# SCH_Embedded_Watch_2023-10-23.net
KiCad netlist of a schematic drawn in EasyEDA
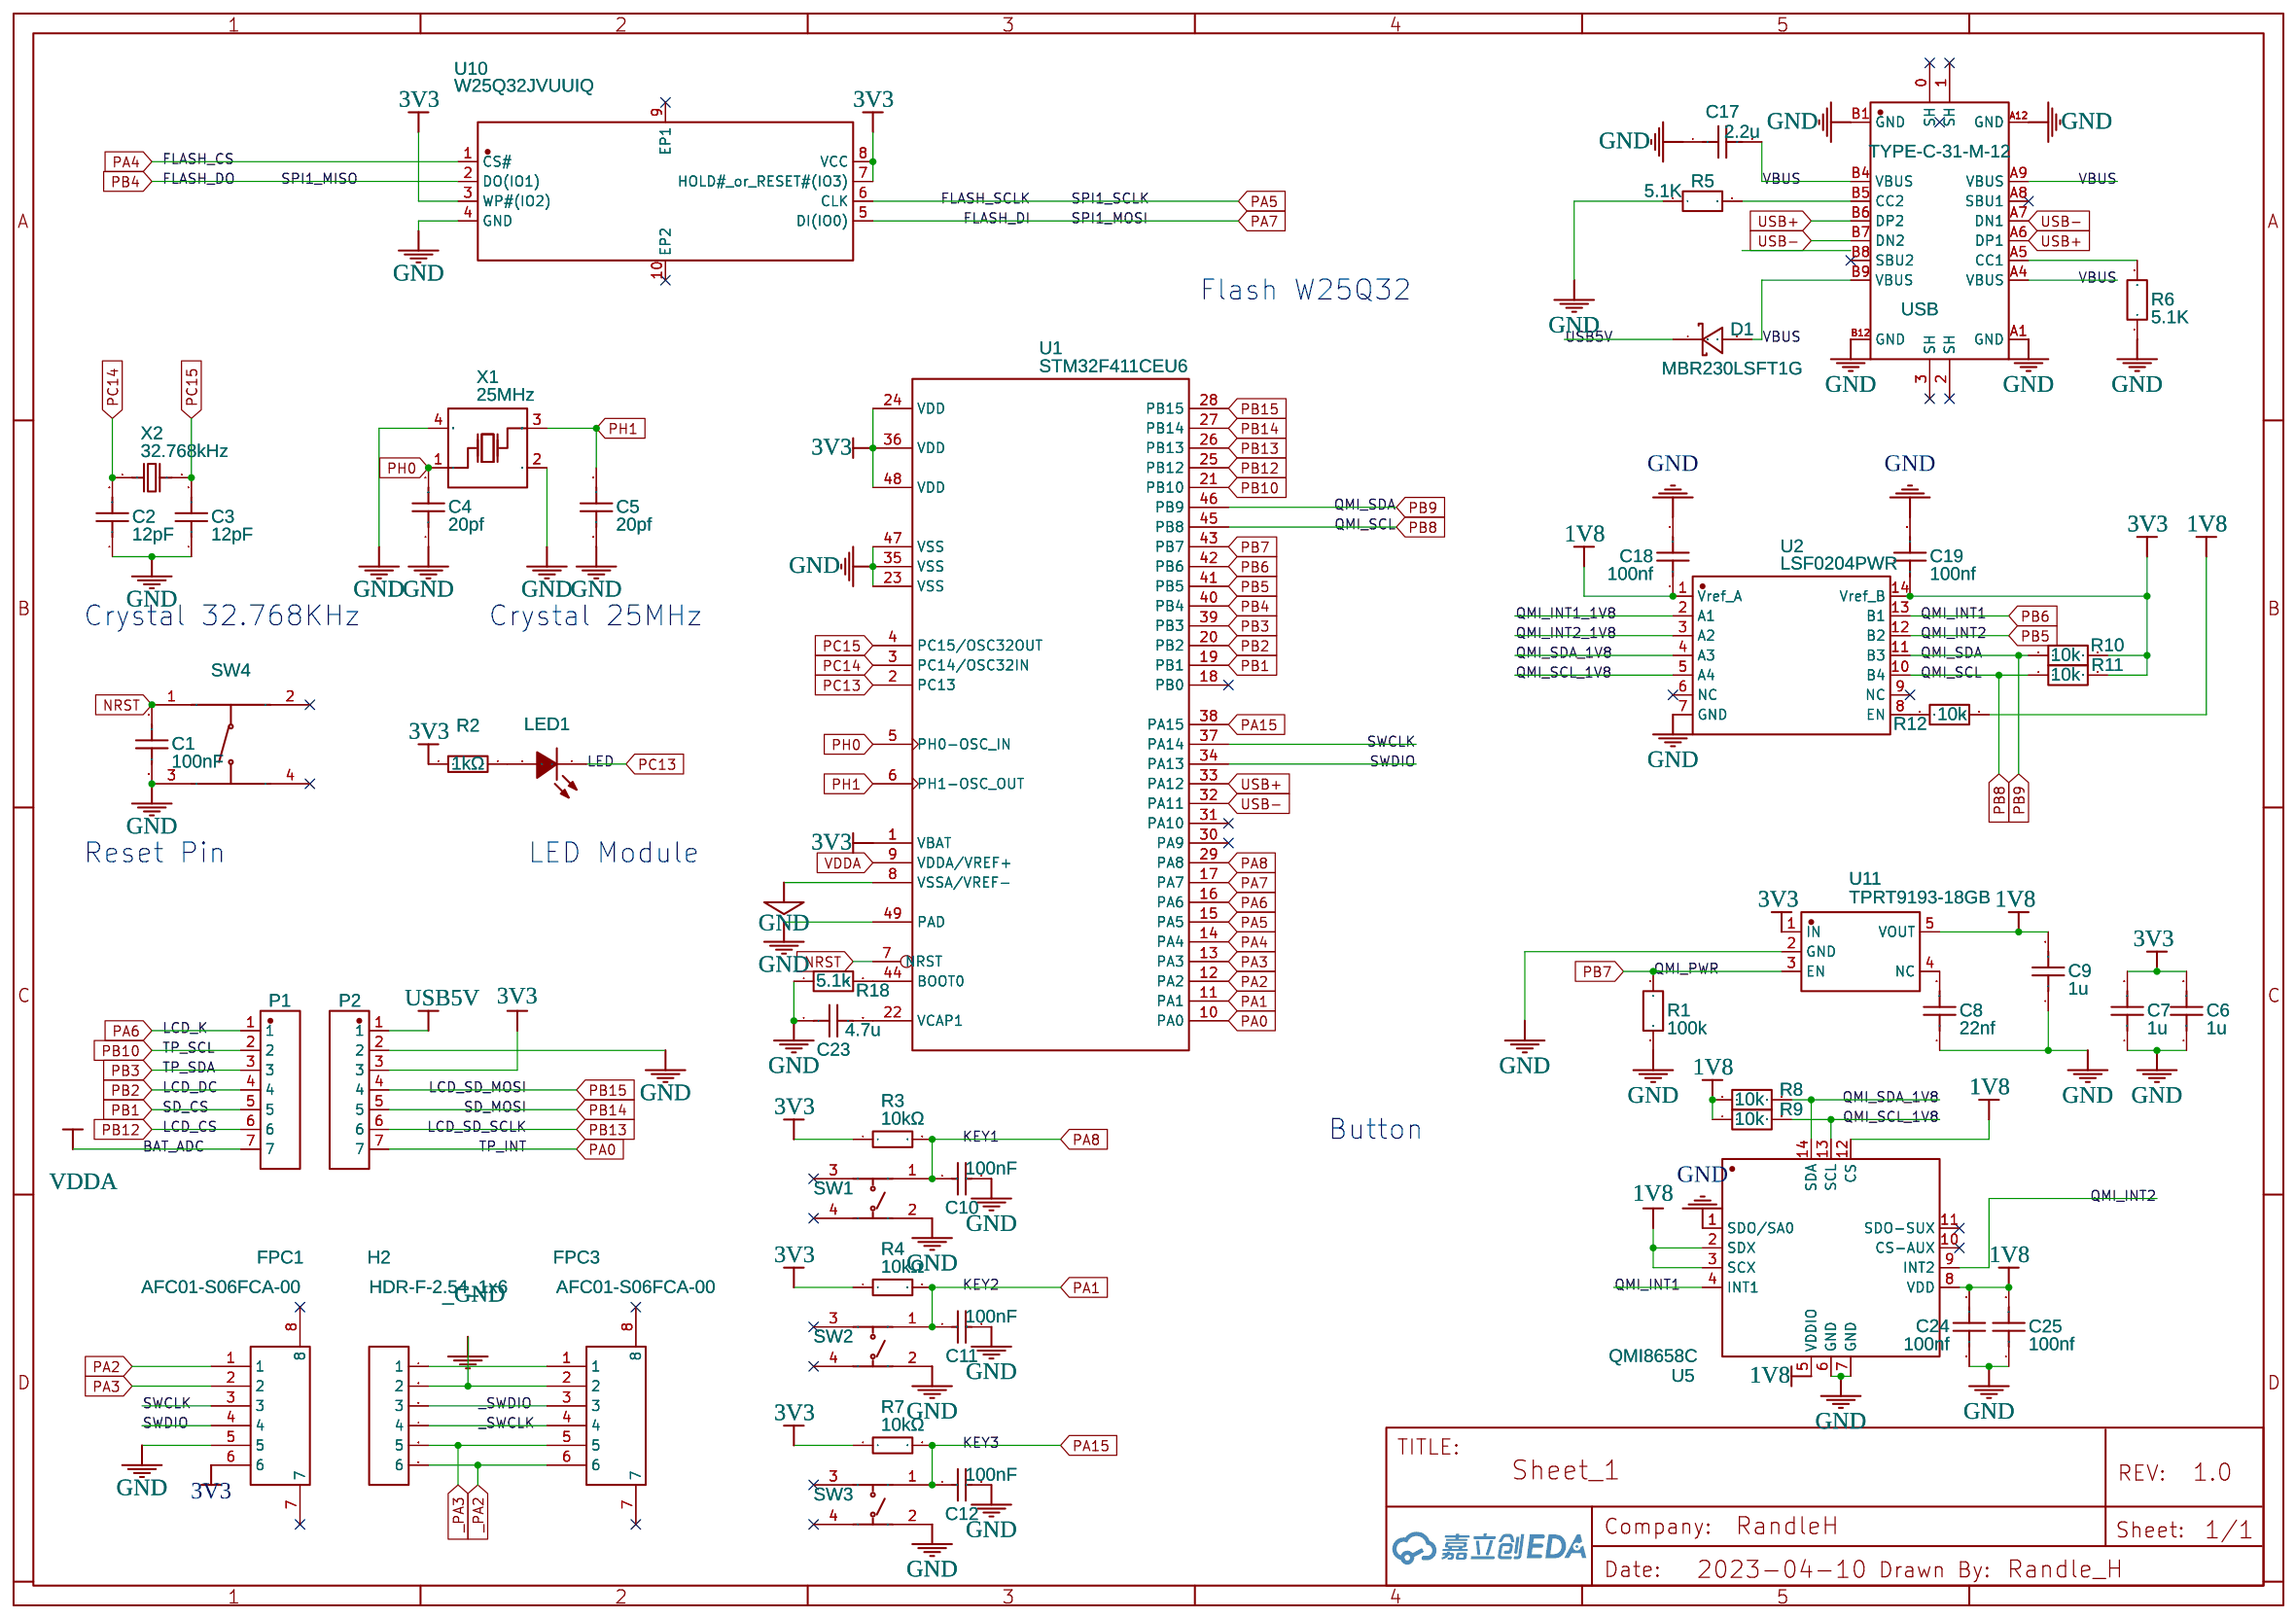
[diagram p0: schematic sheet]

(export (version "E")
  (design (tool "Eeschema 10.0.6"))
  (components
    (comp (ref "C1")
      (value "100nF")
      (fields
        (field (name "Manufacturer Part") "CL05B104KB54PNC")
        (field (name "Manufacturer") "SAMSUNG(三星)")
      )
      (libsource (lib "") (part "CL05B104KB54PNC"))
    )
    (comp (ref "C2")
      (value "12pF")
      (fields
        (field (name "Manufacturer Part") "CC0201JRNPO9BN120")
        (field (name "Manufacturer") "YAGEO(国巨)")
      )
      (libsource (lib "") (part "CC0201JRNPO9BN120"))
    )
    (comp (ref "C3")
      (value "12pF")
      (fields
        (field (name "Manufacturer Part") "CC0201JRNPO9BN120")
        (field (name "Manufacturer") "YAGEO(国巨)")
      )
      (libsource (lib "") (part "CC0201JRNPO9BN120"))
    )
    (comp (ref "C4") (value "20pf") (libsource (lib "") (part "C_0603_US")))
    (comp (ref "C5") (value "20pf") (libsource (lib "") (part "C_0603_US")))
    (comp (ref "C6") (value "1u") (libsource (lib "") (part "C_0603_US")))
    (comp (ref "C7") (value "1u") (libsource (lib "") (part "C_0603_US")))
    (comp (ref "C8") (value "22nf") (libsource (lib "") (part "C_0603_US")))
    (comp (ref "C9") (value "1u") (libsource (lib "") (part "C_0603_US")))
    (comp (ref "C10")
      (value "100nF")
      (fields
        (field (name "Manufacturer Part") "CL05B104KO5NNNC")
        (field (name "Manufacturer") "SAMSUNG(三星)")
      )
      (libsource (lib "") (part "CL05B104KO5NNNC"))
    )
    (comp (ref "C11")
      (value "100nF")
      (fields
        (field (name "Manufacturer Part") "CL05B104KO5NNNC")
        (field (name "Manufacturer") "SAMSUNG(三星)")
      )
      (libsource (lib "") (part "CL05B104KO5NNNC"))
    )
    (comp (ref "C12")
      (value "100nF")
      (fields
        (field (name "Manufacturer Part") "CL05B104KO5NNNC")
        (field (name "Manufacturer") "SAMSUNG(三星)")
      )
      (libsource (lib "") (part "CL05B104KO5NNNC"))
    )
    (comp (ref "C17") (value "2.2u") (libsource (lib "") (part "C_0201_US_2")))
    (comp (ref "C18") (value "100nf") (libsource (lib "") (part "C_0201_US")))
    (comp (ref "C19") (value "100nf") (libsource (lib "") (part "C_0201_US_3")))
    (comp (ref "C23") (value "4.7u") (libsource (lib "") (part "C_0201_US_2")))
    (comp (ref "C24") (value "100nf") (libsource (lib "") (part "C_0201_US_1")))
    (comp (ref "C25") (value "100nf") (libsource (lib "") (part "C_0201_US_3")))
    (comp (ref "D1")
      (value "MBR230LSFT1G")
      (fields (field (name "Manufacturer") "onsemi(安森美)"))
      (libsource (lib "") (part "MBR230LSFT1G"))
    )
    (comp (ref "FPC1")
      (value "AFC01-S06FCA-00")
      (fields (field (name "Manufacturer") "JS(钜硕电子)"))
      (libsource (lib "") (part "AFC01-S06FCA-00"))
    )
    (comp (ref "FPC3")
      (value "AFC01-S06FCA-00")
      (fields (field (name "Manufacturer") "JS(钜硕电子)"))
      (libsource (lib "") (part "AFC01-S06FCA-00"))
    )
    (comp (ref "H2") (value "HDR-F-2.54_1x6") (libsource (lib "") (part "HDR-F-2.54_1x6")))
    (comp (ref "LED1")
      (value "FC-F1005HOK-600H5")
      (fields (field (name "Manufacturer Part") "NCD0402O1") (field (name "Manufacturer") "国星光电"))
      (libsource (lib "") (part "FC-F1005HOK-600H5"))
    )
    (comp (ref "P1")
      (value "PM2.54-1*7")
      (fields
        (field (name "Manufacturer Part") "X6511WVS-07H-C60D48R1")
        (field (name "Manufacturer") "XKB Connectivity(中国星坤)")
      )
      (libsource (lib "") (part "PM2.54-1*7_1"))
    )
    (comp (ref "P2")
      (value "PM2.54-1*7")
      (fields
        (field (name "Manufacturer Part") "X6511WVS-07H-C60D48R1")
        (field (name "Manufacturer") "XKB Connectivity(中国星坤)")
      )
      (libsource (lib "") (part "PM2.54-1*7"))
    )
    (comp (ref "R1") (value "100k") (libsource (lib "") (part "R_0201_EU_2")))
    (comp (ref "R2")
      (value "1kΩ")
      (fields
        (field (name "Manufacturer Part") "0402WGF1001TCE")
        (field (name "Manufacturer") "UNI-ROYAL(厚声)")
      )
      (libsource (lib "") (part "0402WGF1001TCE"))
    )
    (comp (ref "R3")
      (value "10kΩ")
      (fields
        (field (name "Manufacturer Part") "0402WGF1002TCE")
        (field (name "Manufacturer") "UNI-ROYAL(厚声)")
      )
      (libsource (lib "") (part "0402WGF1002TCE"))
    )
    (comp (ref "R4")
      (value "10kΩ")
      (fields
        (field (name "Manufacturer Part") "0402WGF1002TCE")
        (field (name "Manufacturer") "UNI-ROYAL(厚声)")
      )
      (libsource (lib "") (part "0402WGF1002TCE"))
    )
    (comp (ref "R5") (value "5.1K") (libsource (lib "") (part "R_0603_EU")))
    (comp (ref "R6") (value "5.1K") (libsource (lib "") (part "R_0603_EU_1")))
    (comp (ref "R7")
      (value "10kΩ")
      (fields
        (field (name "Manufacturer Part") "0402WGF1002TCE")
        (field (name "Manufacturer") "UNI-ROYAL(厚声)")
      )
      (libsource (lib "") (part "0402WGF1002TCE"))
    )
    (comp (ref "R8") (value "10k") (libsource (lib "") (part "R_0201_EU_1")))
    (comp (ref "R9") (value "10k") (libsource (lib "") (part "R_0201_EU_1")))
    (comp (ref "R10") (value "10k") (libsource (lib "") (part "R_0201_EU_1")))
    (comp (ref "R11") (value "10k") (libsource (lib "") (part "R_0201_EU_1")))
    (comp (ref "R12") (value "10k") (libsource (lib "") (part "R_0201_EU")))
    (comp (ref "R18") (value "5.1k") (libsource (lib "") (part "R_0201_EU_1")))
    (comp (ref "SW1")
      (value "EVQPUD02K")
      (fields (field (name "Manufacturer") "PANASONIC(松下)"))
      (libsource (lib "") (part "EVQPUD02K"))
    )
    (comp (ref "SW2")
      (value "EVQPUD02K")
      (fields (field (name "Manufacturer") "PANASONIC(松下)"))
      (libsource (lib "") (part "EVQPUD02K"))
    )
    (comp (ref "SW3")
      (value "EVQPUD02K")
      (fields (field (name "Manufacturer") "PANASONIC(松下)"))
      (libsource (lib "") (part "EVQPUD02K"))
    )
    (comp (ref "SW4")
      (value "PTS830GM140SMTRLFS")
      (fields (field (name "Manufacturer") "C&K"))
      (libsource (lib "") (part "PTS830GM140SMTRLFS"))
    )
    (comp (ref "U1")
      (value "STM32F411CEU6")
      (fields (field (name "Manufacturer") "ST(意法半导体)"))
      (libsource (lib "") (part "STM32F411CEU6"))
    )
    (comp (ref "U2")
      (value "LSF0204PWR")
      (fields (field (name "Manufacturer") "TI(德州仪器)"))
      (libsource (lib "") (part "LSF0204PWR"))
    )
    (comp (ref "U5")
      (value "QMI8658C")
      (fields (field (name "Manufacturer") "QST(上海矽睿)"))
      (libsource (lib "") (part "QMI8658C"))
    )
    (comp (ref "U10")
      (value "W25Q32JVUUIQ")
      (fields (field (name "Manufacturer") "WINBOND(华邦)"))
      (libsource (lib "") (part "W25Q32JVUUIQ"))
    )
    (comp (ref "U11")
      (value "TPRT9193-18GB")
      (fields (field (name "Manufacturer") "TECH PUBLIC(台舟)"))
      (libsource (lib "") (part "TPRT9193-18GB"))
    )
    (comp (ref "USB")
      (value "TYPE-C-31-M-12")
      (fields (field (name "Manufacturer") "韩国韩荣"))
      (libsource (lib "") (part "TYPE-C-31-M-12"))
    )
    (comp (ref "X1")
      (value "25MHz")
      (fields (field (name "Manufacturer Part") "TAXM25M4RLBCCT2T") (field (name "Manufacturer") "TAE(雅晶鑫)"))
      (libsource (lib "") (part "SMD-3225_4P25MHZ20PF10PPM-40&#126;+85℃"))
    )
    (comp (ref "X2")
      (value "32.768kHz")
      (fields (field (name "Manufacturer Part") "Q13FC1350000400") (field (name "Manufacturer") "EPSON(爱普生)"))
      (libsource (lib "") (part "Q13FC1350000400"))
    )
  )
  (nets
    (net (code "1") (name "/QMI_INT1_1V8") (class "Default")
      (node (ref "U2") (pin "2") (pinfunction "A1_2") (pintype "unspecified"))
    )
    (net (code "2") (name "/QMI_INT2_1V8") (class "Default")
      (node (ref "U2") (pin "3") (pinfunction "A2_3") (pintype "unspecified"))
    )
    (net (code "3") (name "/QMI_SCL_1V8") (class "Default")
      (node (ref "R9") (pin "2") (pinfunction "2_2") (pintype "unspecified"))
      (node (ref "U2") (pin "5") (pinfunction "A4_5") (pintype "unspecified"))
      (node (ref "U5") (pin "13") (pinfunction "SCL_13") (pintype "unspecified"))
    )
    (net (code "4") (name "/QMI_SDA_1V8") (class "Default")
      (node (ref "R8") (pin "2") (pinfunction "2_2") (pintype "unspecified"))
      (node (ref "U2") (pin "4") (pinfunction "A3_4") (pintype "unspecified"))
      (node (ref "U5") (pin "14") (pinfunction "SDA_14") (pintype "unspecified"))
    )
    (net (code "5") (name "/SWCLK") (class "Default")
      (node (ref "FPC1") (pin "3") (pinfunction "3_3") (pintype "unspecified"))
      (node (ref "U1") (pin "37") (pinfunction "PA14_37") (pintype "unspecified"))
    )
    (net (code "6") (name "/SWDIO") (class "Default")
      (node (ref "FPC1") (pin "4") (pinfunction "4_4") (pintype "unspecified"))
      (node (ref "U1") (pin "34") (pinfunction "PA13_34") (pintype "unspecified"))
    )
    (net (code "7") (name "/VBUS") (class "Default")
      (node (ref "C17") (pin "2") (pinfunction "2_2") (pintype "unspecified"))
      (node (ref "D1") (pin "2") (pinfunction "A_2") (pintype "unspecified"))
      (node (ref "USB") (pin "A4") (pinfunction "VBUS_A4") (pintype "unspecified"))
      (node (ref "USB") (pin "A9") (pinfunction "VBUS_A9") (pintype "unspecified"))
      (node (ref "USB") (pin "B4") (pinfunction "VBUS_B4") (pintype "unspecified"))
      (node (ref "USB") (pin "B9") (pinfunction "VBUS_B9") (pintype "unspecified"))
    )
    (net (code "8") (name "/_SWCLK") (class "Default")
      (node (ref "FPC3") (pin "4") (pinfunction "4_4") (pintype "unspecified"))
      (node (ref "H2") (pin "4") (pinfunction "4_4") (pintype "input"))
    )
    (net (code "9") (name "/_SWDIO") (class "Default")
      (node (ref "FPC3") (pin "3") (pinfunction "3_3") (pintype "unspecified"))
      (node (ref "H2") (pin "3") (pinfunction "3_3") (pintype "input"))
    )
    (net (code "10") (name "1V8") (class "Default")
      (node (ref "C18") (pin "1") (pinfunction "1_1") (pintype "unspecified"))
      (node (ref "C24") (pin "1") (pinfunction "1_1") (pintype "unspecified"))
      (node (ref "C25") (pin "2") (pinfunction "2_2") (pintype "unspecified"))
      (node (ref "C9") (pin "2") (pinfunction "2_2") (pintype "unspecified"))
      (node (ref "R12") (pin "1") (pinfunction "1_1") (pintype "unspecified"))
      (node (ref "R8") (pin "1") (pinfunction "1_1") (pintype "unspecified"))
      (node (ref "R9") (pin "1") (pinfunction "1_1") (pintype "unspecified"))
      (node (ref "U11") (pin "5") (pinfunction "VOUT_5") (pintype "unspecified"))
      (node (ref "U2") (pin "1") (pinfunction "Vref_A_1") (pintype "unspecified"))
      (node (ref "U5") (pin "12") (pinfunction "CS_12") (pintype "unspecified"))
      (node (ref "U5") (pin "2") (pinfunction "SDX_2") (pintype "unspecified"))
      (node (ref "U5") (pin "3") (pinfunction "SCX_3") (pintype "unspecified"))
      (node (ref "U5") (pin "5") (pinfunction "VDDIO_5") (pintype "unspecified"))
      (node (ref "U5") (pin "8") (pinfunction "VDD_8") (pintype "unspecified"))
    )
    (net (code "11") (name "3V3") (class "Default")
      (node (ref "C19") (pin "1") (pinfunction "1_1") (pintype "unspecified"))
      (node (ref "C6") (pin "2") (pinfunction "2_2") (pintype "unspecified"))
      (node (ref "C7") (pin "2") (pinfunction "2_2") (pintype "unspecified"))
      (node (ref "FPC1") (pin "6") (pinfunction "6_6") (pintype "unspecified"))
      (node (ref "P2") (pin "3") (pinfunction "3_3") (pintype "unspecified"))
      (node (ref "R10") (pin "2") (pinfunction "2_2") (pintype "unspecified"))
      (node (ref "R11") (pin "2") (pinfunction "2_2") (pintype "unspecified"))
      (node (ref "R2") (pin "1") (pinfunction "1_1") (pintype "input"))
      (node (ref "R3") (pin "1") (pinfunction "1_1") (pintype "input"))
      (node (ref "R4") (pin "1") (pinfunction "1_1") (pintype "input"))
      (node (ref "R7") (pin "1") (pinfunction "1_1") (pintype "input"))
      (node (ref "U1") (pin "1") (pinfunction "VBAT_1") (pintype "passive"))
      (node (ref "U1") (pin "24") (pinfunction "VDD_24") (pintype "unspecified"))
      (node (ref "U1") (pin "36") (pinfunction "VDD_36") (pintype "unspecified"))
      (node (ref "U1") (pin "48") (pinfunction "VDD_48") (pintype "unspecified"))
      (node (ref "U10") (pin "3") (pinfunction "WP#(IO2)_3") (pintype "unspecified"))
      (node (ref "U10") (pin "7") (pinfunction "HOLD#_or_RESET#(IO3)_7") (pintype "unspecified"))
      (node (ref "U10") (pin "8") (pinfunction "VCC_8") (pintype "unspecified"))
      (node (ref "U11") (pin "1") (pinfunction "IN_1") (pintype "unspecified"))
      (node (ref "U2") (pin "14") (pinfunction "Vref_B_14") (pintype "unspecified"))
    )
    (net (code "12") (name "GND") (class "Default")
      (node (ref "C1") (pin "1") (pinfunction "1_1") (pintype "unspecified"))
      (node (ref "C10") (pin "2") (pinfunction "2_2") (pintype "input"))
      (node (ref "C11") (pin "2") (pinfunction "2_2") (pintype "input"))
      (node (ref "C12") (pin "2") (pinfunction "2_2") (pintype "input"))
      (node (ref "C17") (pin "1") (pinfunction "1_1") (pintype "unspecified"))
      (node (ref "C18") (pin "2") (pinfunction "2_2") (pintype "unspecified"))
      (node (ref "C19") (pin "2") (pinfunction "2_2") (pintype "unspecified"))
      (node (ref "C2") (pin "1") (pinfunction "1_1") (pintype "unspecified"))
      (node (ref "C23") (pin "1") (pinfunction "1_1") (pintype "unspecified"))
      (node (ref "C24") (pin "2") (pinfunction "2_2") (pintype "unspecified"))
      (node (ref "C25") (pin "1") (pinfunction "1_1") (pintype "unspecified"))
      (node (ref "C3") (pin "1") (pinfunction "1_1") (pintype "unspecified"))
      (node (ref "C4") (pin "1") (pinfunction "1_1") (pintype "unspecified"))
      (node (ref "C5") (pin "1") (pinfunction "1_1") (pintype "unspecified"))
      (node (ref "C6") (pin "1") (pinfunction "1_1") (pintype "unspecified"))
      (node (ref "C7") (pin "1") (pinfunction "1_1") (pintype "unspecified"))
      (node (ref "C8") (pin "1") (pinfunction "1_1") (pintype "unspecified"))
      (node (ref "C9") (pin "1") (pinfunction "1_1") (pintype "unspecified"))
      (node (ref "FPC1") (pin "5") (pinfunction "5_5") (pintype "unspecified"))
      (node (ref "P2") (pin "2") (pinfunction "2_2") (pintype "unspecified"))
      (node (ref "R1") (pin "2") (pinfunction "2_2") (pintype "unspecified"))
      (node (ref "R18") (pin "1") (pinfunction "1_1") (pintype "unspecified"))
      (node (ref "R5") (pin "1") (pinfunction "1_1") (pintype "unspecified"))
      (node (ref "R6") (pin "1") (pinfunction "1_1") (pintype "unspecified"))
      (node (ref "SW1") (pin "2") (pinfunction "2_2") (pintype "unspecified"))
      (node (ref "SW2") (pin "2") (pinfunction "2_2") (pintype "unspecified"))
      (node (ref "SW3") (pin "2") (pinfunction "2_2") (pintype "unspecified"))
      (node (ref "SW4") (pin "3") (pinfunction "3_3") (pintype "unspecified"))
      (node (ref "U1") (pin "23") (pinfunction "VSS_23") (pintype "unspecified"))
      (node (ref "U1") (pin "35") (pinfunction "VSS_35") (pintype "unspecified"))
      (node (ref "U1") (pin "47") (pinfunction "VSS_47") (pintype "unspecified"))
      (node (ref "U1") (pin "49") (pinfunction "PAD_49") (pintype "passive"))
      (node (ref "U1") (pin "8") (pinfunction "VSSA/VREF-_8") (pintype "passive"))
      (node (ref "U10") (pin "4") (pinfunction "GND_4") (pintype "unspecified"))
      (node (ref "U11") (pin "2") (pinfunction "GND_2") (pintype "unspecified"))
      (node (ref "U2") (pin "7") (pinfunction "GND_7") (pintype "unspecified"))
      (node (ref "U5") (pin "1") (pinfunction "SDO/SA0_1") (pintype "unspecified"))
      (node (ref "U5") (pin "6") (pinfunction "GND_6") (pintype "unspecified"))
      (node (ref "U5") (pin "7") (pinfunction "GND_7") (pintype "unspecified"))
      (node (ref "USB") (pin "A1") (pinfunction "GND_A1") (pintype "unspecified"))
      (node (ref "USB") (pin "A12") (pinfunction "GND_A12") (pintype "unspecified"))
      (node (ref "USB") (pin "B1") (pinfunction "GND_B1") (pintype "unspecified"))
      (node (ref "USB") (pin "B12") (pinfunction "GND_B12") (pintype "unspecified"))
      (node (ref "X1") (pin "2") (pinfunction "GND_2") (pintype "unspecified"))
      (node (ref "X1") (pin "4") (pinfunction "GND_4") (pintype "unspecified"))
    )
    (net (code "13") (name "NRST") (class "Default")
      (node (ref "C1") (pin "2") (pinfunction "2_2") (pintype "unspecified"))
      (node (ref "SW4") (pin "1") (pinfunction "1_1") (pintype "unspecified"))
      (node (ref "U1") (pin "7") (pinfunction "NRST_7") (pintype "unspecified"))
    )
    (net (code "14") (name "Net-(FPC3-Pad1)") (class "Default")
      (node (ref "FPC3") (pin "1") (pinfunction "1_1") (pintype "unspecified"))
      (node (ref "H2") (pin "1") (pinfunction "1_1") (pintype "input"))
    )
    (net (code "15") (name "Net-(LED1-A)") (class "Default")
      (node (ref "LED1") (pin "2") (pinfunction "A_2") (pintype "unspecified"))
      (node (ref "R2") (pin "2") (pinfunction "2_2") (pintype "input"))
    )
    (net (code "16") (name "Net-(U1-BOOT0)") (class "Default")
      (node (ref "R18") (pin "2") (pinfunction "2_2") (pintype "unspecified"))
      (node (ref "U1") (pin "44") (pinfunction "BOOT0_44") (pintype "input"))
    )
    (net (code "17") (name "Net-(U1-VCAP1)") (class "Default")
      (node (ref "C23") (pin "2") (pinfunction "2_2") (pintype "unspecified"))
      (node (ref "U1") (pin "22") (pinfunction "VCAP1_22") (pintype "passive"))
    )
    (net (code "18") (name "Net-(U2-EN)") (class "Default")
      (node (ref "R12") (pin "2") (pinfunction "2_2") (pintype "unspecified"))
      (node (ref "U2") (pin "8") (pinfunction "EN_8") (pintype "unspecified"))
    )
    (net (code "19") (name "Net-(U11-NC)") (class "Default")
      (node (ref "C8") (pin "2") (pinfunction "2_2") (pintype "unspecified"))
      (node (ref "U11") (pin "4") (pinfunction "NC_4") (pintype "unspecified"))
    )
    (net (code "20") (name "Net-(USB-CC1)") (class "Default")
      (node (ref "R6") (pin "2") (pinfunction "2_2") (pintype "unspecified"))
      (node (ref "USB") (pin "A5") (pinfunction "CC1_A5") (pintype "unspecified"))
    )
    (net (code "21") (name "Net-(USB-CC2)") (class "Default")
      (node (ref "R5") (pin "2") (pinfunction "2_2") (pintype "unspecified"))
      (node (ref "USB") (pin "B5") (pinfunction "CC2_B5") (pintype "unspecified"))
    )
    (net (code "22") (name "PA0") (class "Default")
      (node (ref "P2") (pin "7") (pinfunction "7_7") (pintype "unspecified"))
      (node (ref "U1") (pin "10") (pinfunction "PA0_10") (pintype "unspecified"))
    )
    (net (code "23") (name "PA1") (class "Default")
      (node (ref "C11") (pin "1") (pinfunction "1_1") (pintype "input"))
      (node (ref "R4") (pin "2") (pinfunction "2_2") (pintype "input"))
      (node (ref "SW2") (pin "1") (pinfunction "1_1") (pintype "unspecified"))
      (node (ref "U1") (pin "11") (pinfunction "PA1_11") (pintype "unspecified"))
    )
    (net (code "24") (name "PA2") (class "Default")
      (node (ref "FPC1") (pin "1") (pinfunction "1_1") (pintype "unspecified"))
      (node (ref "U1") (pin "12") (pinfunction "PA2_12") (pintype "unspecified"))
    )
    (net (code "25") (name "PA3") (class "Default")
      (node (ref "FPC1") (pin "2") (pinfunction "2_2") (pintype "unspecified"))
      (node (ref "U1") (pin "13") (pinfunction "PA3_13") (pintype "unspecified"))
    )
    (net (code "26") (name "PA4") (class "Default")
      (node (ref "U1") (pin "14") (pinfunction "PA4_14") (pintype "unspecified"))
      (node (ref "U10") (pin "1") (pinfunction "CS#_1") (pintype "unspecified"))
    )
    (net (code "27") (name "PA5") (class "Default")
      (node (ref "U1") (pin "15") (pinfunction "PA5_15") (pintype "unspecified"))
      (node (ref "U10") (pin "6") (pinfunction "CLK_6") (pintype "unspecified"))
    )
    (net (code "28") (name "PA6") (class "Default")
      (node (ref "P1") (pin "1") (pinfunction "1_1") (pintype "unspecified"))
      (node (ref "U1") (pin "16") (pinfunction "PA6_16") (pintype "unspecified"))
    )
    (net (code "29") (name "PA7") (class "Default")
      (node (ref "U1") (pin "17") (pinfunction "PA7_17") (pintype "unspecified"))
      (node (ref "U10") (pin "5") (pinfunction "DI(IO0)_5") (pintype "unspecified"))
    )
    (net (code "30") (name "PA8") (class "Default")
      (node (ref "C10") (pin "1") (pinfunction "1_1") (pintype "input"))
      (node (ref "R3") (pin "2") (pinfunction "2_2") (pintype "input"))
      (node (ref "SW1") (pin "1") (pinfunction "1_1") (pintype "unspecified"))
      (node (ref "U1") (pin "29") (pinfunction "PA8_29") (pintype "unspecified"))
    )
    (net (code "31") (name "PA15") (class "Default")
      (node (ref "C12") (pin "1") (pinfunction "1_1") (pintype "input"))
      (node (ref "R7") (pin "2") (pinfunction "2_2") (pintype "input"))
      (node (ref "SW3") (pin "1") (pinfunction "1_1") (pintype "unspecified"))
      (node (ref "U1") (pin "38") (pinfunction "PA15_38") (pintype "unspecified"))
    )
    (net (code "32") (name "PB1") (class "Default")
      (node (ref "P1") (pin "5") (pinfunction "5_5") (pintype "unspecified"))
      (node (ref "U1") (pin "19") (pinfunction "PB1_19") (pintype "unspecified"))
    )
    (net (code "33") (name "PB2") (class "Default")
      (node (ref "P1") (pin "4") (pinfunction "4_4") (pintype "unspecified"))
      (node (ref "U1") (pin "20") (pinfunction "PB2_20") (pintype "unspecified"))
    )
    (net (code "34") (name "PB3") (class "Default")
      (node (ref "P1") (pin "3") (pinfunction "3_3") (pintype "unspecified"))
      (node (ref "U1") (pin "39") (pinfunction "PB3_39") (pintype "unspecified"))
    )
    (net (code "35") (name "PB4") (class "Default")
      (node (ref "U1") (pin "40") (pinfunction "PB4_40") (pintype "unspecified"))
      (node (ref "U10") (pin "2") (pinfunction "DO(IO1)_2") (pintype "unspecified"))
    )
    (net (code "36") (name "PB5") (class "Default")
      (node (ref "U1") (pin "41") (pinfunction "PB5_41") (pintype "unspecified"))
      (node (ref "U2") (pin "12") (pinfunction "B2_12") (pintype "unspecified"))
      (node (ref "U5") (pin "9") (pinfunction "INT2_9") (pintype "unspecified"))
    )
    (net (code "37") (name "PB6") (class "Default")
      (node (ref "U1") (pin "42") (pinfunction "PB6_42") (pintype "unspecified"))
      (node (ref "U2") (pin "13") (pinfunction "B1_13") (pintype "unspecified"))
      (node (ref "U5") (pin "4") (pinfunction "INT1_4") (pintype "unspecified"))
    )
    (net (code "38") (name "PB7") (class "Default")
      (node (ref "R1") (pin "1") (pinfunction "1_1") (pintype "unspecified"))
      (node (ref "U1") (pin "43") (pinfunction "PB7_43") (pintype "unspecified"))
      (node (ref "U11") (pin "3") (pinfunction "EN_3") (pintype "unspecified"))
    )
    (net (code "39") (name "PB8") (class "Default")
      (node (ref "R11") (pin "1") (pinfunction "1_1") (pintype "unspecified"))
      (node (ref "U1") (pin "45") (pinfunction "PB8_45") (pintype "unspecified"))
      (node (ref "U2") (pin "10") (pinfunction "B4_10") (pintype "unspecified"))
    )
    (net (code "40") (name "PB9") (class "Default")
      (node (ref "R10") (pin "1") (pinfunction "1_1") (pintype "unspecified"))
      (node (ref "U1") (pin "46") (pinfunction "PB9_46") (pintype "unspecified"))
      (node (ref "U2") (pin "11") (pinfunction "B3_11") (pintype "unspecified"))
    )
    (net (code "41") (name "PB10") (class "Default")
      (node (ref "P1") (pin "2") (pinfunction "2_2") (pintype "unspecified"))
      (node (ref "U1") (pin "21") (pinfunction "PB10_21") (pintype "unspecified"))
    )
    (net (code "42") (name "PB12") (class "Default")
      (node (ref "P1") (pin "6") (pinfunction "6_6") (pintype "unspecified"))
      (node (ref "U1") (pin "25") (pinfunction "PB12_25") (pintype "unspecified"))
    )
    (net (code "43") (name "PB13") (class "Default")
      (node (ref "P2") (pin "6") (pinfunction "6_6") (pintype "unspecified"))
      (node (ref "U1") (pin "26") (pinfunction "PB13_26") (pintype "unspecified"))
    )
    (net (code "44") (name "PB14") (class "Default")
      (node (ref "P2") (pin "5") (pinfunction "5_5") (pintype "unspecified"))
      (node (ref "U1") (pin "27") (pinfunction "PB14_27") (pintype "unspecified"))
    )
    (net (code "45") (name "PB15") (class "Default")
      (node (ref "P2") (pin "4") (pinfunction "4_4") (pintype "unspecified"))
      (node (ref "U1") (pin "28") (pinfunction "PB15_28") (pintype "unspecified"))
    )
    (net (code "46") (name "PC13") (class "Default")
      (node (ref "LED1") (pin "1") (pinfunction "K_1") (pintype "unspecified"))
      (node (ref "U1") (pin "2") (pinfunction "PC13_2") (pintype "unspecified"))
    )
    (net (code "47") (name "PC14") (class "Default")
      (node (ref "C2") (pin "2") (pinfunction "2_2") (pintype "unspecified"))
      (node (ref "U1") (pin "3") (pinfunction "PC14/OSC32IN_3") (pintype "unspecified"))
      (node (ref "X2") (pin "1") (pinfunction "1_1") (pintype "unspecified"))
    )
    (net (code "48") (name "PC15") (class "Default")
      (node (ref "C3") (pin "2") (pinfunction "2_2") (pintype "unspecified"))
      (node (ref "U1") (pin "4") (pinfunction "PC15/OSC32OUT_4") (pintype "unspecified"))
      (node (ref "X2") (pin "2") (pinfunction "2_2") (pintype "unspecified"))
    )
    (net (code "49") (name "PH0") (class "Default")
      (node (ref "C4") (pin "2") (pinfunction "2_2") (pintype "unspecified"))
      (node (ref "U1") (pin "5") (pinfunction "PH0-OSC_IN_5") (pintype "unspecified"))
      (node (ref "X1") (pin "1") (pinfunction "OSC1_1") (pintype "unspecified"))
    )
    (net (code "50") (name "PH1") (class "Default")
      (node (ref "C5") (pin "2") (pinfunction "2_2") (pintype "unspecified"))
      (node (ref "U1") (pin "6") (pinfunction "PH1-OSC_OUT_6") (pintype "unspecified"))
      (node (ref "X1") (pin "3") (pinfunction "OSC2_3") (pintype "unspecified"))
    )
    (net (code "51") (name "USB+") (class "Default")
      (node (ref "U1") (pin "33") (pinfunction "PA12_33") (pintype "unspecified"))
      (node (ref "USB") (pin "A6") (pinfunction "DP1_A6") (pintype "unspecified"))
      (node (ref "USB") (pin "B6") (pinfunction "DP2_B6") (pintype "unspecified"))
    )
    (net (code "52") (name "USB-") (class "Default")
      (node (ref "U1") (pin "32") (pinfunction "PA11_32") (pintype "unspecified"))
      (node (ref "USB") (pin "A7") (pinfunction "DN1_A7") (pintype "unspecified"))
      (node (ref "USB") (pin "B7") (pinfunction "DN2_B7") (pintype "unspecified"))
    )
    (net (code "53") (name "USB5V") (class "Default")
      (node (ref "D1") (pin "1") (pinfunction "C_1") (pintype "unspecified"))
      (node (ref "P2") (pin "1") (pinfunction "1_1") (pintype "unspecified"))
    )
    (net (code "54") (name "VDDA") (class "Default")
      (node (ref "P1") (pin "7") (pinfunction "7_7") (pintype "unspecified"))
      (node (ref "U1") (pin "9") (pinfunction "VDDA/VREF+_9") (pintype "passive"))
    )
    (net (code "55") (name "_GND") (class "Default")
      (node (ref "FPC3") (pin "2") (pinfunction "2_2") (pintype "unspecified"))
      (node (ref "H2") (pin "2") (pinfunction "2_2") (pintype "input"))
    )
    (net (code "56") (name "_PA2") (class "Default")
      (node (ref "FPC3") (pin "6") (pinfunction "6_6") (pintype "unspecified"))
      (node (ref "H2") (pin "6") (pinfunction "6_6") (pintype "input"))
    )
    (net (code "57") (name "_PA3") (class "Default")
      (node (ref "FPC3") (pin "5") (pinfunction "5_5") (pintype "unspecified"))
      (node (ref "H2") (pin "5") (pinfunction "5_5") (pintype "input"))
    )
    (net (code "58") (name "unconnected-(FPC1-Pad7)") (class "Default")
      (node (ref "FPC1") (pin "7") (pinfunction "7_7") (pintype "unspecified+no_connect"))
    )
    (net (code "59") (name "unconnected-(FPC1-Pad8)") (class "Default")
      (node (ref "FPC1") (pin "8") (pinfunction "8_8") (pintype "unspecified+no_connect"))
    )
    (net (code "60") (name "unconnected-(FPC3-Pad7)") (class "Default")
      (node (ref "FPC3") (pin "7") (pinfunction "7_7") (pintype "unspecified+no_connect"))
    )
    (net (code "61") (name "unconnected-(FPC3-Pad8)") (class "Default")
      (node (ref "FPC3") (pin "8") (pinfunction "8_8") (pintype "unspecified+no_connect"))
    )
    (net (code "62") (name "unconnected-(SW1-Pad3)") (class "Default")
      (node (ref "SW1") (pin "3") (pinfunction "3_3") (pintype "unspecified+no_connect"))
    )
    (net (code "63") (name "unconnected-(SW1-Pad4)") (class "Default")
      (node (ref "SW1") (pin "4") (pinfunction "4_4") (pintype "unspecified+no_connect"))
    )
    (net (code "64") (name "unconnected-(SW2-Pad3)") (class "Default")
      (node (ref "SW2") (pin "3") (pinfunction "3_3") (pintype "unspecified+no_connect"))
    )
    (net (code "65") (name "unconnected-(SW2-Pad4)") (class "Default")
      (node (ref "SW2") (pin "4") (pinfunction "4_4") (pintype "unspecified+no_connect"))
    )
    (net (code "66") (name "unconnected-(SW3-Pad3)") (class "Default")
      (node (ref "SW3") (pin "3") (pinfunction "3_3") (pintype "unspecified+no_connect"))
    )
    (net (code "67") (name "unconnected-(SW3-Pad4)") (class "Default")
      (node (ref "SW3") (pin "4") (pinfunction "4_4") (pintype "unspecified+no_connect"))
    )
    (net (code "68") (name "unconnected-(SW4-Pad2)") (class "Default")
      (node (ref "SW4") (pin "2") (pinfunction "2_2") (pintype "unspecified+no_connect"))
    )
    (net (code "69") (name "unconnected-(SW4-Pad4)") (class "Default")
      (node (ref "SW4") (pin "4") (pinfunction "4_4") (pintype "unspecified+no_connect"))
    )
    (net (code "70") (name "unconnected-(U1-PA9-Pad30)") (class "Default")
      (node (ref "U1") (pin "30") (pinfunction "PA9_30") (pintype "unspecified+no_connect"))
    )
    (net (code "71") (name "unconnected-(U1-PA10-Pad31)") (class "Default")
      (node (ref "U1") (pin "31") (pinfunction "PA10_31") (pintype "unspecified+no_connect"))
    )
    (net (code "72") (name "unconnected-(U1-PB0-Pad18)") (class "Default")
      (node (ref "U1") (pin "18") (pinfunction "PB0_18") (pintype "unspecified+no_connect"))
    )
    (net (code "73") (name "unconnected-(U2-NC-Pad6)") (class "Default")
      (node (ref "U2") (pin "6") (pinfunction "NC_6") (pintype "unspecified+no_connect"))
    )
    (net (code "74") (name "unconnected-(U2-NC-Pad9)") (class "Default")
      (node (ref "U2") (pin "9") (pinfunction "NC_9") (pintype "unspecified+no_connect"))
    )
    (net (code "75") (name "unconnected-(U5-CS-AUX-Pad10)") (class "Default")
      (node (ref "U5") (pin "10") (pinfunction "CS-AUX_10") (pintype "unspecified+no_connect"))
    )
    (net (code "76") (name "unconnected-(U5-SDO-SUX-Pad11)") (class "Default")
      (node (ref "U5") (pin "11") (pinfunction "SDO-SUX_11") (pintype "unspecified+no_connect"))
    )
    (net (code "77") (name "unconnected-(U10-EP1-Pad9)") (class "Default")
      (node (ref "U10") (pin "9") (pinfunction "EP1_9") (pintype "unspecified+no_connect"))
    )
    (net (code "78") (name "unconnected-(U10-EP2-Pad10)") (class "Default")
      (node (ref "U10") (pin "10") (pinfunction "EP2_10") (pintype "unspecified+no_connect"))
    )
    (net (code "79") (name "unconnected-(USB-SBU1-PadA8)") (class "Default")
      (node (ref "USB") (pin "A8") (pinfunction "SBU1_A8") (pintype "unspecified+no_connect"))
    )
    (net (code "80") (name "unconnected-(USB-SBU2-PadB8)") (class "Default")
      (node (ref "USB") (pin "B8") (pinfunction "SBU2_B8") (pintype "unspecified+no_connect"))
    )
    (net (code "81") (name "unconnected-(USB-SH-Pad0)") (class "Default")
      (node (ref "USB") (pin "0") (pinfunction "SH_0") (pintype "unspecified+no_connect"))
    )
    (net (code "82") (name "unconnected-(USB-SH-Pad1)") (class "Default")
      (node (ref "USB") (pin "1") (pinfunction "SH_1") (pintype "unspecified+no_connect"))
    )
    (net (code "83") (name "unconnected-(USB-SH-Pad2)") (class "Default")
      (node (ref "USB") (pin "2") (pinfunction "SH_2") (pintype "unspecified+no_connect"))
    )
    (net (code "84") (name "unconnected-(USB-SH-Pad3)") (class "Default")
      (node (ref "USB") (pin "3") (pinfunction "SH_3") (pintype "unspecified+no_connect"))
    )
  )
)
